# ard_connector.net
KiCad netlist of a schematic drawn in Altium Designer
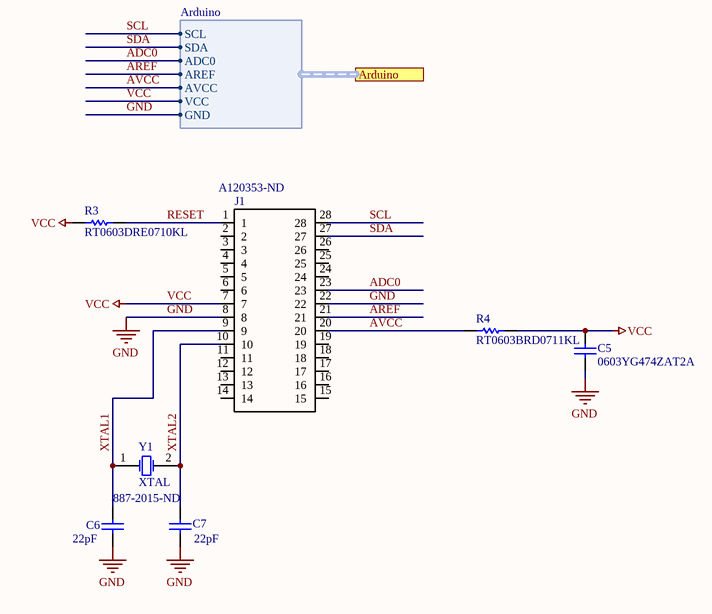
[diagram p0: ard_connector.SchDoc]

(export (version "E")
  (design (tool "Eeschema 10.0.6"))
  (components
    (comp (ref "C5")
      (value "0603YG474ZAT2A")
      (footprint "CAPC1608X90X35ML15T15")
      (fields (field (name "MANUFACTURER") "AVX Interconnect / Elco"))
      (libsource (lib "Altium Content Vault") (part "CAP"))
    )
    (comp (ref "C6")
      (value "CL10C220JB8NNNC")
      (footprint "CAPC1608X90X30LL10T20")
      (description "Chip Capacitor, 22 pF, +/- 5%, 50 V, -55 to 125 degC, 0603 (1608 Metric), RoHS, Tape and Reel")
      (fields (field (name "MANUFACTURER") "Samsung Electro-Mechanics") (field (name "CAPACITANCE") "22pF"))
      (libsource (lib "Altium Content Vault") (part "CAP-NP-2"))
    )
    (comp (ref "C7")
      (value "CL10C220JB8NNNC")
      (footprint "CAPC1608X90X30LL10T20")
      (description "Chip Capacitor, 22 pF, +/- 5%, 50 V, -55 to 125 degC, 0603 (1608 Metric), RoHS, Tape and Reel")
      (fields (field (name "MANUFACTURER") "Samsung Electro-Mechanics") (field (name "CAPACITANCE") "22pF"))
      (libsource (lib "Altium Content Vault") (part "CAP-NP-2"))
    )
    (comp (ref "J1")
      (value "1-2199298-9")
      (footprint "*DIP762W60P254L3556H510Q28")
      (description "CONN IC DIP SOCKET 28POS TIN")
      (fields
        (field (name "DIGI-KEY_PART_NUMBER") "A120353-ND")
        (field (name "MF") "TE Connectivity")
        (field (name "SUPPLIER PART NUMBER 1") "A120353-ND")
      )
      (libsource (lib "1-2199298-9") (part "1-2199298-9"))
    )
    (comp (ref "R3")
      (value "RT0603DRE0710KL")
      (footprint "RESC1608X55X25ML10T15")
      (fields (field (name "MANUFACTURER") "Yageo"))
      (libsource (lib "Altium Content Vault") (part "RES"))
    )
    (comp (ref "R4")
      (value "RT0603BRD0711KL")
      (footprint "RESC1608X55X25LL10T15")
      (fields (field (name "MANUFACTURER") "Yageo"))
      (libsource (lib "Altium Content Vault") (part "RES"))
    )
    (comp (ref "Y1")
      (value "XTAL")
      (footprint "R38")
      (description "CRYSTAL 16.000MHZ 20PF THRU")
      (fields
        (field (name "SUPPLIER PART NUMBER 1") "887-2015-ND")
        (field (name "MANUFACTURER") "TXC")
        (field (name "MANUFACTURER PART NUMBER") "9B-16.000MBBK-B")
        (field (name "PUBLISHER") "Altium Limited")
      )
      (libsource (lib "Miscellaneous Devices") (part "XTAL"))
    )
  )
  (nets
    (net (code "2") (name "/ADC0") (class "Default")
      (node (ref "J1") (pin "23") (pinfunction "23_23") (pintype "passive"))
    )
    (net (code "3") (name "/AREF") (class "Default")
      (node (ref "J1") (pin "21") (pinfunction "21_21") (pintype "passive"))
    )
    (net (code "4") (name "/AVCC") (class "Default")
      (node (ref "J1") (pin "20") (pinfunction "20_20") (pintype "passive"))
      (node (ref "R4") (pin "1") (pinfunction "1_1") (pintype "passive"))
    )
    (net (code "5") (name "/RESET") (class "Default")
      (node (ref "J1") (pin "1") (pinfunction "1_1") (pintype "passive"))
      (node (ref "R3") (pin "2") (pinfunction "2_2") (pintype "passive"))
    )
    (net (code "6") (name "/SCL") (class "Default")
      (node (ref "J1") (pin "28") (pinfunction "28_28") (pintype "passive"))
    )
    (net (code "7") (name "/SDA") (class "Default")
      (node (ref "J1") (pin "27") (pinfunction "27_27") (pintype "passive"))
    )
    (net (code "8") (name "/XTAL1") (class "Default")
      (node (ref "C6") (pin "2") (pinfunction "2_2") (pintype "passive"))
      (node (ref "J1") (pin "9") (pinfunction "9_9") (pintype "passive"))
      (node (ref "Y1") (pin "1") (pinfunction "OSC1_1") (pintype "passive"))
    )
    (net (code "9") (name "/XTAL2") (class "Default")
      (node (ref "C7") (pin "2") (pinfunction "2_2") (pintype "passive"))
      (node (ref "J1") (pin "10") (pinfunction "10_10") (pintype "passive"))
      (node (ref "Y1") (pin "2") (pinfunction "OSC2_2") (pintype "passive"))
    )
    (net (code "11") (name "GND") (class "Default")
      (node (ref "C5") (pin "1") (pinfunction "1_1") (pintype "passive"))
      (node (ref "C6") (pin "1") (pinfunction "1_1") (pintype "passive"))
      (node (ref "C7") (pin "1") (pinfunction "1_1") (pintype "passive"))
      (node (ref "J1") (pin "22") (pinfunction "22_22") (pintype "passive"))
      (node (ref "J1") (pin "8") (pinfunction "8_8") (pintype "passive"))
    )
    (net (code "12") (name "VCC") (class "Default")
      (node (ref "C5") (pin "2") (pinfunction "2_2") (pintype "passive"))
      (node (ref "J1") (pin "7") (pinfunction "7_7") (pintype "passive"))
      (node (ref "R3") (pin "1") (pinfunction "1_1") (pintype "passive"))
      (node (ref "R4") (pin "2") (pinfunction "2_2") (pintype "passive"))
    )
    (net (code "13") (name "unconnected-(J1-Pad2)") (class "Default")
      (node (ref "J1") (pin "2") (pinfunction "2_2") (pintype "passive"))
    )
    (net (code "14") (name "unconnected-(J1-Pad3)") (class "Default")
      (node (ref "J1") (pin "3") (pinfunction "3_3") (pintype "passive"))
    )
    (net (code "15") (name "unconnected-(J1-Pad4)") (class "Default")
      (node (ref "J1") (pin "4") (pinfunction "4_4") (pintype "passive"))
    )
    (net (code "16") (name "unconnected-(J1-Pad5)") (class "Default")
      (node (ref "J1") (pin "5") (pinfunction "5_5") (pintype "passive"))
    )
    (net (code "17") (name "unconnected-(J1-Pad6)") (class "Default")
      (node (ref "J1") (pin "6") (pinfunction "6_6") (pintype "passive"))
    )
    (net (code "18") (name "unconnected-(J1-Pad11)") (class "Default")
      (node (ref "J1") (pin "11") (pinfunction "11_11") (pintype "passive"))
    )
    (net (code "19") (name "unconnected-(J1-Pad12)") (class "Default")
      (node (ref "J1") (pin "12") (pinfunction "12_12") (pintype "passive"))
    )
    (net (code "20") (name "unconnected-(J1-Pad13)") (class "Default")
      (node (ref "J1") (pin "13") (pinfunction "13_13") (pintype "passive"))
    )
    (net (code "21") (name "unconnected-(J1-Pad14)") (class "Default")
      (node (ref "J1") (pin "14") (pinfunction "14_14") (pintype "passive"))
    )
    (net (code "22") (name "unconnected-(J1-Pad15)") (class "Default")
      (node (ref "J1") (pin "15") (pinfunction "15_15") (pintype "passive"))
    )
    (net (code "23") (name "unconnected-(J1-Pad16)") (class "Default")
      (node (ref "J1") (pin "16") (pinfunction "16_16") (pintype "passive"))
    )
    (net (code "24") (name "unconnected-(J1-Pad17)") (class "Default")
      (node (ref "J1") (pin "17") (pinfunction "17_17") (pintype "passive"))
    )
    (net (code "25") (name "unconnected-(J1-Pad18)") (class "Default")
      (node (ref "J1") (pin "18") (pinfunction "18_18") (pintype "passive"))
    )
    (net (code "26") (name "unconnected-(J1-Pad19)") (class "Default")
      (node (ref "J1") (pin "19") (pinfunction "19_19") (pintype "passive"))
    )
    (net (code "27") (name "unconnected-(J1-Pad24)") (class "Default")
      (node (ref "J1") (pin "24") (pinfunction "24_24") (pintype "passive"))
    )
    (net (code "28") (name "unconnected-(J1-Pad25)") (class "Default")
      (node (ref "J1") (pin "25") (pinfunction "25_25") (pintype "passive"))
    )
    (net (code "29") (name "unconnected-(J1-Pad26)") (class "Default")
      (node (ref "J1") (pin "26") (pinfunction "26_26") (pintype "passive"))
    )
  )
)
